# hv_psu_v100_FLYBACK.net
KiCad netlist of a schematic drawn in Altium Designer
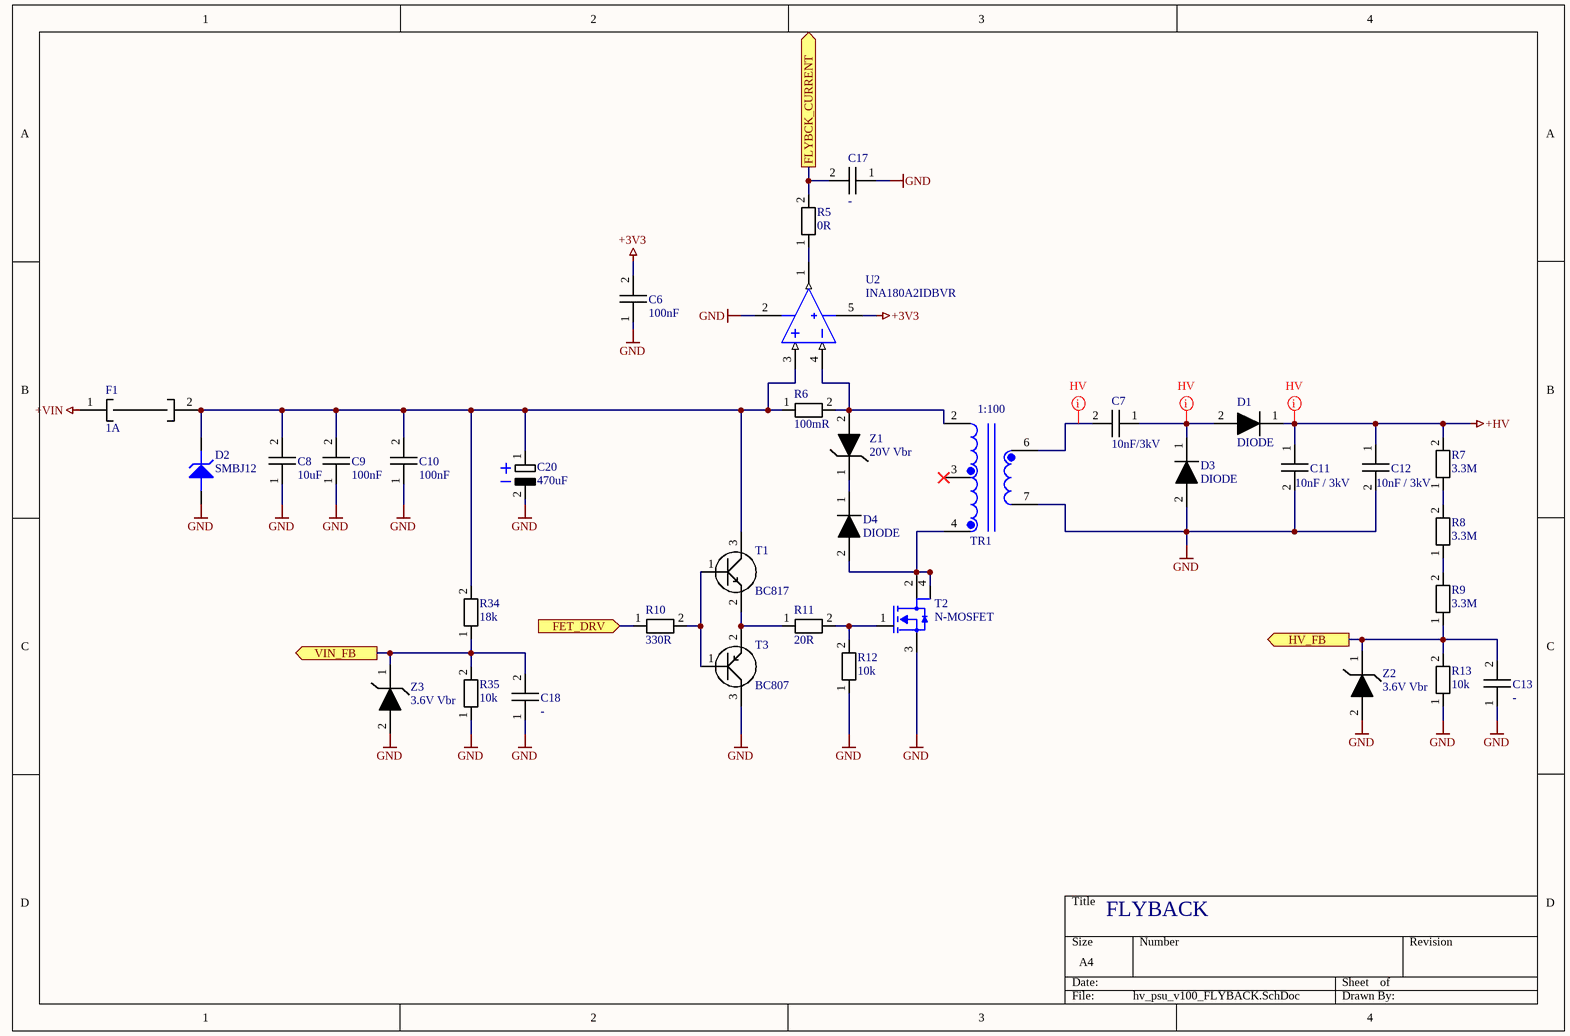
[diagram p0: hv_psu_v100_FLYBACK.SchDoc]

(export (version "E")
  (design (tool "Eeschema 10.0.6"))
  (components
    (comp (ref "C6") (value "100nF") (footprint "1206_C") (libsource (lib "Schlib1") (part "CAPACITOR")))
    (comp (ref "C7") (value "10nF/3kV") (footprint "2220_C") (libsource (lib "Schlib1") (part "CAPACITOR")))
    (comp (ref "C8") (value "10uF") (footprint "1206_C") (libsource (lib "Schlib1") (part "CAPACITOR")))
    (comp (ref "C9") (value "100nF") (footprint "1206_C") (libsource (lib "Schlib1") (part "CAPACITOR")))
    (comp (ref "C10") (value "100nF") (footprint "1206_C") (libsource (lib "Schlib1") (part "CAPACITOR")))
    (comp (ref "C11")
      (value "10nF / 3kV")
      (footprint "2220_C")
      (libsource (lib "Schlib1") (part "CAPACITOR"))
    )
    (comp (ref "C12")
      (value "10nF / 3kV")
      (footprint "2220_C")
      (libsource (lib "Schlib1") (part "CAPACITOR"))
    )
    (comp (ref "C13") (value "-") (footprint "1206_C") (libsource (lib "Schlib1") (part "CAPACITOR")))
    (comp (ref "C17") (value "-") (footprint "1206_C") (libsource (lib "Schlib1") (part "CAPACITOR")))
    (comp (ref "C18") (value "-") (footprint "1206_C") (libsource (lib "Schlib1") (part "CAPACITOR")))
    (comp (ref "C20")
      (value "470uF")
      (footprint "CAPAE9383X110M")
      (libsource (lib "Schlib1") (part "CAPACITOR_ELCO"))
    )
    (comp (ref "D1") (value "DIODE") (footprint "DIODE_400MIL") (libsource (lib "Schlib1") (part "DIODE")))
    (comp (ref "D2")
      (value "SMBJ12")
      (footprint "DO-214AA (SMB)")
      (libsource (lib "Schlib1") (part "DIODE_TVS"))
    )
    (comp (ref "D3") (value "DIODE") (footprint "DIODE_400MIL") (libsource (lib "Schlib1") (part "DIODE")))
    (comp (ref "D4") (value "DIODE") (footprint "DIODE_400MIL") (libsource (lib "Schlib1") (part "DIODE")))
    (comp (ref "F1") (value "1A") (footprint "FUSE_1812L") (libsource (lib "Schlib1") (part "FUSE")))
    (comp (ref "R5") (value "0R") (footprint "1206") (libsource (lib "Schlib1") (part "RESISTOR")))
    (comp (ref "R6") (value "100mR") (footprint "1206") (libsource (lib "Schlib1") (part "RESISTOR")))
    (comp (ref "R7") (value "3.3M") (footprint "1206") (libsource (lib "Schlib1") (part "RESISTOR")))
    (comp (ref "R8") (value "3.3M") (footprint "1206") (libsource (lib "Schlib1") (part "RESISTOR")))
    (comp (ref "R9") (value "3.3M") (footprint "1206") (libsource (lib "Schlib1") (part "RESISTOR")))
    (comp (ref "R10") (value "330R") (footprint "1206") (libsource (lib "Schlib1") (part "RESISTOR")))
    (comp (ref "R11") (value "20R") (footprint "1206") (libsource (lib "Schlib1") (part "RESISTOR")))
    (comp (ref "R12") (value "10k") (footprint "1206") (libsource (lib "Schlib1") (part "RESISTOR")))
    (comp (ref "R13") (value "10k") (footprint "1206") (libsource (lib "Schlib1") (part "RESISTOR")))
    (comp (ref "R34") (value "18k") (footprint "1206") (libsource (lib "Schlib1") (part "RESISTOR")))
    (comp (ref "R35") (value "10k") (footprint "1206") (libsource (lib "Schlib1") (part "RESISTOR")))
    (comp (ref "T1") (value "BC817") (footprint "SOT23") (libsource (lib "Schlib1") (part "TRANSISTOR_NPN")))
    (comp (ref "T2")
      (value "N-MOSFET")
      (footprint "SOT233-1")
      (description "Power N-MOSFET 100V@1.5A 500mR 1.25W SOT223")
      (libsource (lib "Schlib1") (part "IRLL110"))
    )
    (comp (ref "T3") (value "BC807") (footprint "SOT23") (libsource (lib "Schlib1") (part "TRANSISTOR_PNP")))
    (comp (ref "TR1")
      (value "DARFON_CCFL_TRANSFORMER")
      (footprint "DARFON_CCFL_TRANSFORMER")
      (libsource (lib "Schlib1") (part "DARFON_CCFL_TRANSFORMER"))
    )
    (comp (ref "U2")
      (value "INA180A2IDBVR")
      (footprint "SOT23-5")
      (description "Current Sense Amplifiers MULTI CHANNEL CURRENT SENSE L/H SIDE")
      (fields (field (name "MOUSER PART NUMBER") "595-INA180A2IDBVR"))
      (libsource (lib "ic_modules") (part "INA180A2IDBVR"))
    )
    (comp (ref "Z1")
      (value "20V Vbr")
      (footprint "SMD_DIODE_SOD80")
      (libsource (lib "Schlib1") (part "DIODE_ZENER"))
    )
    (comp (ref "Z2")
      (value "3.6V Vbr")
      (footprint "SMD_DIODE_SOD80")
      (libsource (lib "Schlib1") (part "DIODE_ZENER"))
    )
    (comp (ref "Z3")
      (value "3.6V Vbr")
      (footprint "SMD_DIODE_SOD80")
      (libsource (lib "Schlib1") (part "DIODE_ZENER"))
    )
  )
  (nets
    (net (code "1") (name "+3V3") (class "Default")
      (node (ref "C6") (pin "2") (pinfunction "2_2") (pintype "passive"))
      (node (ref "U2") (pin "5") (pinfunction "V+_5") (pintype "power_in"))
    )
    (net (code "2") (name "+HV") (class "Default")
      (node (ref "C11") (pin "1") (pinfunction "1_1") (pintype "passive"))
      (node (ref "C12") (pin "1") (pinfunction "1_1") (pintype "passive"))
      (node (ref "D1") (pin "1") (pinfunction "1_1") (pintype "passive"))
      (node (ref "R7") (pin "2") (pinfunction "1_2") (pintype "passive"))
    )
    (net (code "3") (name "+VIN") (class "Default")
      (node (ref "F1") (pin "1") (pinfunction "1_1") (pintype "passive"))
    )
    (net (code "4") (name "/FET_DRV") (class "Default")
      (node (ref "R10") (pin "1") (pinfunction "0_1") (pintype "passive"))
    )
    (net (code "5") (name "/FLYBCK_CURRENT") (class "Default")
      (node (ref "C17") (pin "2") (pinfunction "2_2") (pintype "passive"))
      (node (ref "R5") (pin "2") (pinfunction "1_2") (pintype "passive"))
    )
    (net (code "6") (name "/HV_FB") (class "Default")
      (node (ref "C13") (pin "2") (pinfunction "2_2") (pintype "passive"))
      (node (ref "R13") (pin "2") (pinfunction "1_2") (pintype "passive"))
      (node (ref "R9") (pin "1") (pinfunction "0_1") (pintype "passive"))
      (node (ref "Z2") (pin "1") (pinfunction "1_1") (pintype "passive"))
    )
    (net (code "7") (name "/VIN_FB") (class "Default")
      (node (ref "C18") (pin "2") (pinfunction "2_2") (pintype "passive"))
      (node (ref "R34") (pin "1") (pinfunction "0_1") (pintype "passive"))
      (node (ref "R35") (pin "2") (pinfunction "1_2") (pintype "passive"))
      (node (ref "Z3") (pin "1") (pinfunction "1_1") (pintype "passive"))
    )
    (net (code "8") (name "GND") (class "Default")
      (node (ref "C10") (pin "1") (pinfunction "1_1") (pintype "passive"))
      (node (ref "C11") (pin "2") (pinfunction "2_2") (pintype "passive"))
      (node (ref "C12") (pin "2") (pinfunction "2_2") (pintype "passive"))
      (node (ref "C13") (pin "1") (pinfunction "1_1") (pintype "passive"))
      (node (ref "C17") (pin "1") (pinfunction "1_1") (pintype "passive"))
      (node (ref "C18") (pin "1") (pinfunction "1_1") (pintype "passive"))
      (node (ref "C20") (pin "2") (pinfunction "2_2") (pintype "passive"))
      (node (ref "C6") (pin "1") (pinfunction "1_1") (pintype "passive"))
      (node (ref "C8") (pin "1") (pinfunction "1_1") (pintype "passive"))
      (node (ref "C9") (pin "1") (pinfunction "1_1") (pintype "passive"))
      (node (ref "D2") (pin "A") (pinfunction "A_A") (pintype "passive"))
      (node (ref "D3") (pin "2") (pinfunction "2_2") (pintype "passive"))
      (node (ref "R12") (pin "1") (pinfunction "0_1") (pintype "passive"))
      (node (ref "R13") (pin "1") (pinfunction "0_1") (pintype "passive"))
      (node (ref "R35") (pin "1") (pinfunction "0_1") (pintype "passive"))
      (node (ref "T2") (pin "3") (pinfunction "S_3") (pintype "passive"))
      (node (ref "T3") (pin "3") (pinfunction "3_3") (pintype "passive"))
      (node (ref "TR1") (pin "7") (pinfunction "4_7") (pintype "passive"))
      (node (ref "U2") (pin "2") (pinfunction "V-_2") (pintype "power_in"))
      (node (ref "Z2") (pin "2") (pinfunction "2_2") (pintype "passive"))
      (node (ref "Z3") (pin "2") (pinfunction "2_2") (pintype "passive"))
    )
    (net (code "9") (name "Net-(C7-Pad1)") (class "Default")
      (node (ref "C7") (pin "1") (pinfunction "1_1") (pintype "passive"))
      (node (ref "D1") (pin "2") (pinfunction "2_2") (pintype "passive"))
      (node (ref "D3") (pin "1") (pinfunction "1_1") (pintype "passive"))
    )
    (net (code "10") (name "Net-(C7-Pad2)") (class "Default")
      (node (ref "C7") (pin "2") (pinfunction "2_2") (pintype "passive"))
      (node (ref "TR1") (pin "6") (pinfunction "6_6") (pintype "passive"))
    )
    (net (code "11") (name "Net-(D4-Pad1)") (class "Default")
      (node (ref "D4") (pin "1") (pinfunction "1_1") (pintype "passive"))
      (node (ref "Z1") (pin "1") (pinfunction "1_1") (pintype "passive"))
    )
    (net (code "12") (name "Net-(R5-0)") (class "Default")
      (node (ref "R5") (pin "1") (pinfunction "0_1") (pintype "passive"))
      (node (ref "U2") (pin "1") (pinfunction "OUT_1") (pintype "output"))
    )
    (net (code "13") (name "Net-(R6-1)") (class "Default")
      (node (ref "R6") (pin "2") (pinfunction "1_2") (pintype "passive"))
      (node (ref "TR1") (pin "2") (pinfunction "1_2") (pintype "passive"))
      (node (ref "U2") (pin "4") (pinfunction "IN-_4") (pintype "input"))
      (node (ref "Z1") (pin "2") (pinfunction "2_2") (pintype "passive"))
    )
    (net (code "14") (name "Net-(R7-0)") (class "Default")
      (node (ref "R7") (pin "1") (pinfunction "0_1") (pintype "passive"))
      (node (ref "R8") (pin "2") (pinfunction "1_2") (pintype "passive"))
    )
    (net (code "15") (name "Net-(R8-0)") (class "Default")
      (node (ref "R8") (pin "1") (pinfunction "0_1") (pintype "passive"))
      (node (ref "R9") (pin "2") (pinfunction "1_2") (pintype "passive"))
    )
    (net (code "16") (name "Net-(R10-1)") (class "Default")
      (node (ref "R10") (pin "2") (pinfunction "1_2") (pintype "passive"))
      (node (ref "T1") (pin "1") (pinfunction "1_1") (pintype "passive"))
      (node (ref "T3") (pin "1") (pinfunction "1_1") (pintype "passive"))
    )
    (net (code "17") (name "Net-(R11-0)") (class "Default")
      (node (ref "R11") (pin "1") (pinfunction "0_1") (pintype "passive"))
      (node (ref "T1") (pin "2") (pinfunction "2_2") (pintype "passive"))
      (node (ref "T3") (pin "2") (pinfunction "2_2") (pintype "passive"))
    )
    (net (code "18") (name "Net-(R11-1)") (class "Default")
      (node (ref "R11") (pin "2") (pinfunction "1_2") (pintype "passive"))
      (node (ref "R12") (pin "2") (pinfunction "1_2") (pintype "passive"))
      (node (ref "T2") (pin "1") (pinfunction "G_1") (pintype "passive"))
    )
    (net (code "19") (name "Net-(R34-1)") (class "Default")
      (node (ref "C10") (pin "2") (pinfunction "2_2") (pintype "passive"))
      (node (ref "C20") (pin "1") (pinfunction "1_1") (pintype "passive"))
      (node (ref "C8") (pin "2") (pinfunction "2_2") (pintype "passive"))
      (node (ref "C9") (pin "2") (pinfunction "2_2") (pintype "passive"))
      (node (ref "D2") (pin "K") (pinfunction "K_K") (pintype "passive"))
      (node (ref "F1") (pin "2") (pinfunction "2_2") (pintype "passive"))
      (node (ref "R34") (pin "2") (pinfunction "1_2") (pintype "passive"))
      (node (ref "R6") (pin "1") (pinfunction "0_1") (pintype "passive"))
      (node (ref "T1") (pin "3") (pinfunction "3_3") (pintype "passive"))
      (node (ref "U2") (pin "3") (pinfunction "IN+_3") (pintype "input"))
    )
    (net (code "20") (name "Net-(TR1-3)") (class "Default")
      (node (ref "D4") (pin "2") (pinfunction "2_2") (pintype "passive"))
      (node (ref "T2") (pin "2") (pinfunction "D_2") (pintype "passive"))
      (node (ref "T2") (pin "4") (pinfunction "D_4") (pintype "passive"))
      (node (ref "TR1") (pin "4") (pinfunction "3_4") (pintype "passive"))
    )
    (net (code "21") (name "unconnected-(TR1-2-Pad3)") (class "Default")
      (node (ref "TR1") (pin "3") (pinfunction "2_3") (pintype "passive+no_connect"))
    )
  )
)
